# LED.net
KiCad netlist of a schematic drawn in Altium Designer
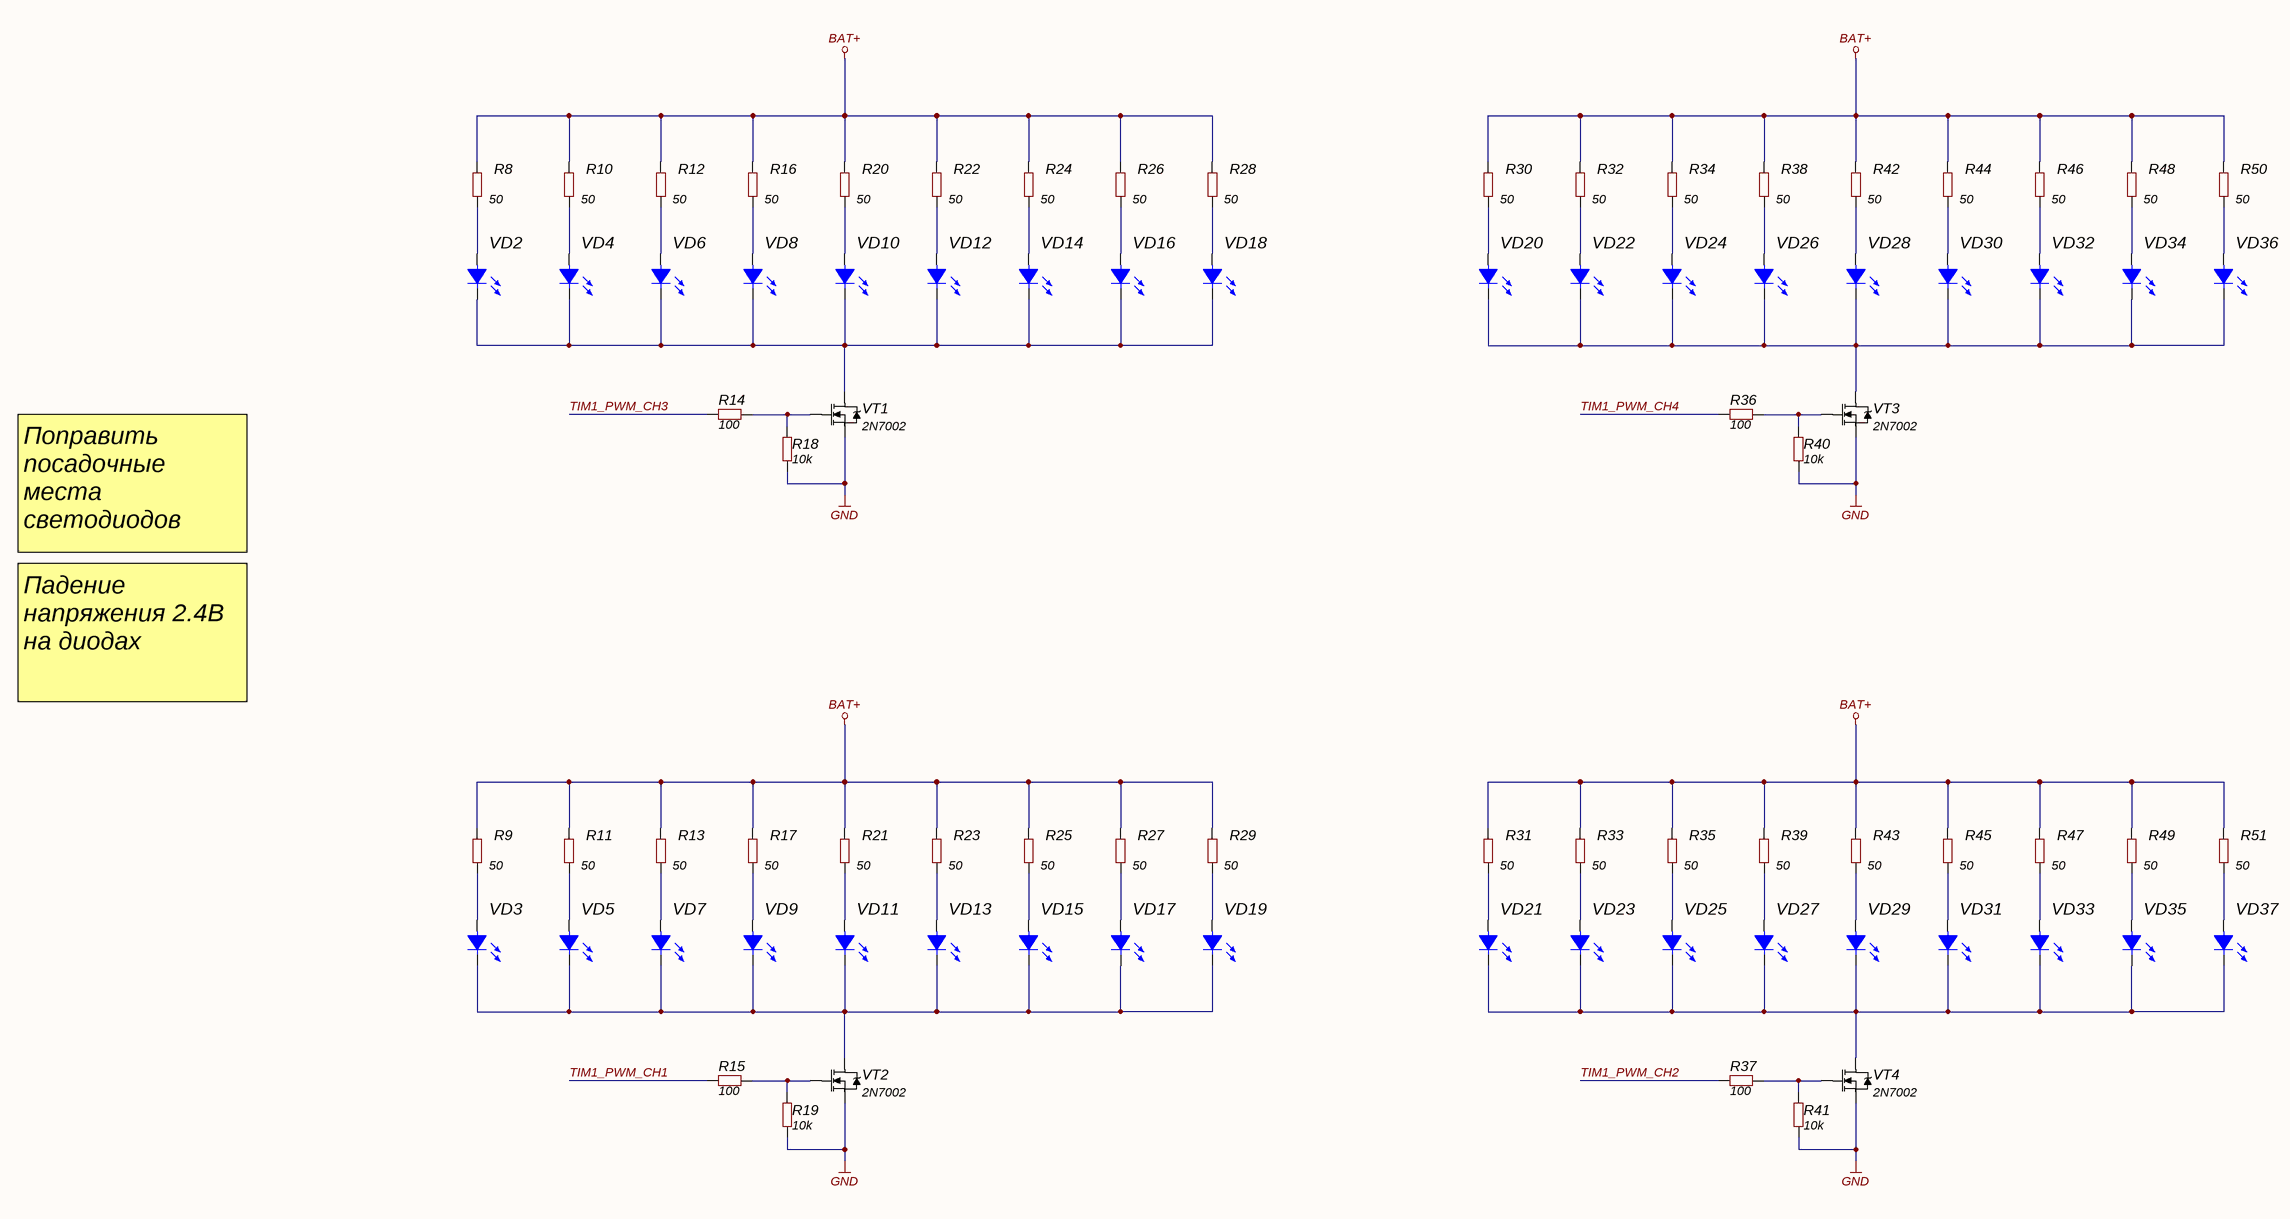
[diagram p0: LED.SchDoc]

(export (version "E")
  (design (tool "Eeschema 10.0.6"))
  (components
    (comp (ref "R8")
      (value "50")
      (footprint "RES: 0603")
      (fields
        (field (name "MANUFACTURER") "Yageo")
        (field (name "PARTNUMBER") "RC0603JR-07100RL")
        (field (name "VALUEMANUFACTURERPARTNUMBER") "Resistor film, 50, , 0603, 0.1W, -55...+125°C")
      )
      (libsource (lib "resistor") (part "Resistor_0603"))
    )
    (comp (ref "R9")
      (value "50")
      (footprint "RES: 0603")
      (fields
        (field (name "MANUFACTURER") "Yageo")
        (field (name "PARTNUMBER") "RC0603JR-07100RL")
        (field (name "VALUEMANUFACTURERPARTNUMBER") "Resistor film, 50, , 0603, 0.1W, -55...+125°C")
      )
      (libsource (lib "resistor") (part "Resistor_0603"))
    )
    (comp (ref "R10")
      (value "50")
      (footprint "RES: 0603")
      (fields
        (field (name "MANUFACTURER") "Yageo")
        (field (name "PARTNUMBER") "RC0603JR-07100RL")
        (field (name "VALUEMANUFACTURERPARTNUMBER") "Resistor film, 50, , 0603, 0.1W, -55...+125°C")
      )
      (libsource (lib "resistor") (part "Resistor_0603"))
    )
    (comp (ref "R11")
      (value "50")
      (footprint "RES: 0603")
      (fields
        (field (name "MANUFACTURER") "Yageo")
        (field (name "PARTNUMBER") "RC0603JR-07100RL")
        (field (name "VALUEMANUFACTURERPARTNUMBER") "Resistor film, 50, , 0603, 0.1W, -55...+125°C")
      )
      (libsource (lib "resistor") (part "Resistor_0603"))
    )
    (comp (ref "R12")
      (value "50")
      (footprint "RES: 0603")
      (fields
        (field (name "MANUFACTURER") "Yageo")
        (field (name "PARTNUMBER") "RC0603JR-07100RL")
        (field (name "VALUEMANUFACTURERPARTNUMBER") "Resistor film, 50, , 0603, 0.1W, -55...+125°C")
      )
      (libsource (lib "resistor") (part "Resistor_0603"))
    )
    (comp (ref "R13")
      (value "50")
      (footprint "RES: 0603")
      (fields
        (field (name "MANUFACTURER") "Yageo")
        (field (name "PARTNUMBER") "RC0603JR-07100RL")
        (field (name "VALUEMANUFACTURERPARTNUMBER") "Resistor film, 50, , 0603, 0.1W, -55...+125°C")
      )
      (libsource (lib "resistor") (part "Resistor_0603"))
    )
    (comp (ref "R14")
      (value "100")
      (footprint "RES: 0603")
      (fields
        (field (name "MANUFACTURER") "Yageo")
        (field (name "PARTNUMBER") "RC0603JR-07100RL")
        (field (name "VALUEMANUFACTURERPARTNUMBER") "Resistor film, 100, , 0603, 0.1W, -55...+125°C")
      )
      (libsource (lib "") (part "Resistor_0603_1"))
    )
    (comp (ref "R15")
      (value "100")
      (footprint "RES: 0603")
      (fields
        (field (name "MANUFACTURER") "Yageo")
        (field (name "PARTNUMBER") "RC0603JR-07100RL")
        (field (name "VALUEMANUFACTURERPARTNUMBER") "Resistor film, 100, , 0603, 0.1W, -55...+125°C")
      )
      (libsource (lib "") (part "Resistor_0603_1"))
    )
    (comp (ref "R16")
      (value "50")
      (footprint "RES: 0603")
      (fields
        (field (name "MANUFACTURER") "Yageo")
        (field (name "PARTNUMBER") "RC0603JR-07100RL")
        (field (name "VALUEMANUFACTURERPARTNUMBER") "Resistor film, 50, , 0603, 0.1W, -55...+125°C")
      )
      (libsource (lib "resistor") (part "Resistor_0603"))
    )
    (comp (ref "R17")
      (value "50")
      (footprint "RES: 0603")
      (fields
        (field (name "MANUFACTURER") "Yageo")
        (field (name "PARTNUMBER") "RC0603JR-07100RL")
        (field (name "VALUEMANUFACTURERPARTNUMBER") "Resistor film, 50, , 0603, 0.1W, -55...+125°C")
      )
      (libsource (lib "resistor") (part "Resistor_0603"))
    )
    (comp (ref "R18")
      (value "10k")
      (footprint "RES: 0603")
      (fields
        (field (name "MANUFACTURER") "Yageo")
        (field (name "PARTNUMBER") "RC0603JR-07100RL")
        (field (name "VALUEMANUFACTURERPARTNUMBER") "Resistor film, 10k, , 0603, 0.1W, -55...+125°C")
      )
      (libsource (lib "resistor") (part "Resistor_0603"))
    )
    (comp (ref "R19")
      (value "10k")
      (footprint "RES: 0603")
      (fields
        (field (name "MANUFACTURER") "Yageo")
        (field (name "PARTNUMBER") "RC0603JR-07100RL")
        (field (name "VALUEMANUFACTURERPARTNUMBER") "Resistor film, 10k, , 0603, 0.1W, -55...+125°C")
      )
      (libsource (lib "resistor") (part "Resistor_0603"))
    )
    (comp (ref "R20")
      (value "50")
      (footprint "RES: 0603")
      (fields
        (field (name "MANUFACTURER") "Yageo")
        (field (name "PARTNUMBER") "RC0603JR-07100RL")
        (field (name "VALUEMANUFACTURERPARTNUMBER") "Resistor film, 50, , 0603, 0.1W, -55...+125°C")
      )
      (libsource (lib "resistor") (part "Resistor_0603"))
    )
    (comp (ref "R21")
      (value "50")
      (footprint "RES: 0603")
      (fields
        (field (name "MANUFACTURER") "Yageo")
        (field (name "PARTNUMBER") "RC0603JR-07100RL")
        (field (name "VALUEMANUFACTURERPARTNUMBER") "Resistor film, 50, , 0603, 0.1W, -55...+125°C")
      )
      (libsource (lib "resistor") (part "Resistor_0603"))
    )
    (comp (ref "R22")
      (value "50")
      (footprint "RES: 0603")
      (fields
        (field (name "MANUFACTURER") "Yageo")
        (field (name "PARTNUMBER") "RC0603JR-07100RL")
        (field (name "VALUEMANUFACTURERPARTNUMBER") "Resistor film, 50, , 0603, 0.1W, -55...+125°C")
      )
      (libsource (lib "resistor") (part "Resistor_0603"))
    )
    (comp (ref "R23")
      (value "50")
      (footprint "RES: 0603")
      (fields
        (field (name "MANUFACTURER") "Yageo")
        (field (name "PARTNUMBER") "RC0603JR-07100RL")
        (field (name "VALUEMANUFACTURERPARTNUMBER") "Resistor film, 50, , 0603, 0.1W, -55...+125°C")
      )
      (libsource (lib "resistor") (part "Resistor_0603"))
    )
    (comp (ref "R24")
      (value "50")
      (footprint "RES: 0603")
      (fields
        (field (name "MANUFACTURER") "Yageo")
        (field (name "PARTNUMBER") "RC0603JR-07100RL")
        (field (name "VALUEMANUFACTURERPARTNUMBER") "Resistor film, 50, , 0603, 0.1W, -55...+125°C")
      )
      (libsource (lib "resistor") (part "Resistor_0603"))
    )
    (comp (ref "R25")
      (value "50")
      (footprint "RES: 0603")
      (fields
        (field (name "MANUFACTURER") "Yageo")
        (field (name "PARTNUMBER") "RC0603JR-07100RL")
        (field (name "VALUEMANUFACTURERPARTNUMBER") "Resistor film, 50, , 0603, 0.1W, -55...+125°C")
      )
      (libsource (lib "resistor") (part "Resistor_0603"))
    )
    (comp (ref "R26")
      (value "50")
      (footprint "RES: 0603")
      (fields
        (field (name "MANUFACTURER") "Yageo")
        (field (name "PARTNUMBER") "RC0603JR-07100RL")
        (field (name "VALUEMANUFACTURERPARTNUMBER") "Resistor film, 50, , 0603, 0.1W, -55...+125°C")
      )
      (libsource (lib "resistor") (part "Resistor_0603"))
    )
    (comp (ref "R27")
      (value "50")
      (footprint "RES: 0603")
      (fields
        (field (name "MANUFACTURER") "Yageo")
        (field (name "PARTNUMBER") "RC0603JR-07100RL")
        (field (name "VALUEMANUFACTURERPARTNUMBER") "Resistor film, 50, , 0603, 0.1W, -55...+125°C")
      )
      (libsource (lib "resistor") (part "Resistor_0603"))
    )
    (comp (ref "R28")
      (value "50")
      (footprint "RES: 0603")
      (fields
        (field (name "MANUFACTURER") "Yageo")
        (field (name "PARTNUMBER") "RC0603JR-07100RL")
        (field (name "VALUEMANUFACTURERPARTNUMBER") "Resistor film, 50, , 0603, 0.1W, -55...+125°C")
      )
      (libsource (lib "resistor") (part "Resistor_0603"))
    )
    (comp (ref "R29")
      (value "50")
      (footprint "RES: 0603")
      (fields
        (field (name "MANUFACTURER") "Yageo")
        (field (name "PARTNUMBER") "RC0603JR-07100RL")
        (field (name "VALUEMANUFACTURERPARTNUMBER") "Resistor film, 50, , 0603, 0.1W, -55...+125°C")
      )
      (libsource (lib "resistor") (part "Resistor_0603"))
    )
    (comp (ref "R30")
      (value "50")
      (footprint "RES: 0603")
      (fields
        (field (name "MANUFACTURER") "Yageo")
        (field (name "PARTNUMBER") "RC0603JR-07100RL")
        (field (name "VALUEMANUFACTURERPARTNUMBER") "Resistor film, 50, , 0603, 0.1W, -55...+125°C")
      )
      (libsource (lib "resistor") (part "Resistor_0603"))
    )
    (comp (ref "R31")
      (value "50")
      (footprint "RES: 0603")
      (fields
        (field (name "MANUFACTURER") "Yageo")
        (field (name "PARTNUMBER") "RC0603JR-07100RL")
        (field (name "VALUEMANUFACTURERPARTNUMBER") "Resistor film, 50, , 0603, 0.1W, -55...+125°C")
      )
      (libsource (lib "resistor") (part "Resistor_0603"))
    )
    (comp (ref "R32")
      (value "50")
      (footprint "RES: 0603")
      (fields
        (field (name "MANUFACTURER") "Yageo")
        (field (name "PARTNUMBER") "RC0603JR-07100RL")
        (field (name "VALUEMANUFACTURERPARTNUMBER") "Resistor film, 50, , 0603, 0.1W, -55...+125°C")
      )
      (libsource (lib "resistor") (part "Resistor_0603"))
    )
    (comp (ref "R33")
      (value "50")
      (footprint "RES: 0603")
      (fields
        (field (name "MANUFACTURER") "Yageo")
        (field (name "PARTNUMBER") "RC0603JR-07100RL")
        (field (name "VALUEMANUFACTURERPARTNUMBER") "Resistor film, 50, , 0603, 0.1W, -55...+125°C")
      )
      (libsource (lib "resistor") (part "Resistor_0603"))
    )
    (comp (ref "R34")
      (value "50")
      (footprint "RES: 0603")
      (fields
        (field (name "MANUFACTURER") "Yageo")
        (field (name "PARTNUMBER") "RC0603JR-07100RL")
        (field (name "VALUEMANUFACTURERPARTNUMBER") "Resistor film, 50, , 0603, 0.1W, -55...+125°C")
      )
      (libsource (lib "resistor") (part "Resistor_0603"))
    )
    (comp (ref "R35")
      (value "50")
      (footprint "RES: 0603")
      (fields
        (field (name "MANUFACTURER") "Yageo")
        (field (name "PARTNUMBER") "RC0603JR-07100RL")
        (field (name "VALUEMANUFACTURERPARTNUMBER") "Resistor film, 50, , 0603, 0.1W, -55...+125°C")
      )
      (libsource (lib "resistor") (part "Resistor_0603"))
    )
    (comp (ref "R36")
      (value "100")
      (footprint "RES: 0603")
      (fields
        (field (name "MANUFACTURER") "Yageo")
        (field (name "PARTNUMBER") "RC0603JR-07100RL")
        (field (name "VALUEMANUFACTURERPARTNUMBER") "Resistor film, 100, , 0603, 0.1W, -55...+125°C")
      )
      (libsource (lib "") (part "Resistor_0603_1"))
    )
    (comp (ref "R37")
      (value "100")
      (footprint "RES: 0603")
      (fields
        (field (name "MANUFACTURER") "Yageo")
        (field (name "PARTNUMBER") "RC0603JR-07100RL")
        (field (name "VALUEMANUFACTURERPARTNUMBER") "Resistor film, 100, , 0603, 0.1W, -55...+125°C")
      )
      (libsource (lib "") (part "Resistor_0603_1"))
    )
    (comp (ref "R38")
      (value "50")
      (footprint "RES: 0603")
      (fields
        (field (name "MANUFACTURER") "Yageo")
        (field (name "PARTNUMBER") "RC0603JR-07100RL")
        (field (name "VALUEMANUFACTURERPARTNUMBER") "Resistor film, 50, , 0603, 0.1W, -55...+125°C")
      )
      (libsource (lib "resistor") (part "Resistor_0603"))
    )
    (comp (ref "R39")
      (value "50")
      (footprint "RES: 0603")
      (fields
        (field (name "MANUFACTURER") "Yageo")
        (field (name "PARTNUMBER") "RC0603JR-07100RL")
        (field (name "VALUEMANUFACTURERPARTNUMBER") "Resistor film, 50, , 0603, 0.1W, -55...+125°C")
      )
      (libsource (lib "resistor") (part "Resistor_0603"))
    )
    (comp (ref "R40")
      (value "10k")
      (footprint "RES: 0603")
      (fields
        (field (name "MANUFACTURER") "Yageo")
        (field (name "PARTNUMBER") "RC0603JR-07100RL")
        (field (name "VALUEMANUFACTURERPARTNUMBER") "Resistor film, 10k, , 0603, 0.1W, -55...+125°C")
      )
      (libsource (lib "resistor") (part "Resistor_0603"))
    )
    (comp (ref "R41")
      (value "10k")
      (footprint "RES: 0603")
      (fields
        (field (name "MANUFACTURER") "Yageo")
        (field (name "PARTNUMBER") "RC0603JR-07100RL")
        (field (name "VALUEMANUFACTURERPARTNUMBER") "Resistor film, 10k, , 0603, 0.1W, -55...+125°C")
      )
      (libsource (lib "resistor") (part "Resistor_0603"))
    )
    (comp (ref "R42")
      (value "50")
      (footprint "RES: 0603")
      (fields
        (field (name "MANUFACTURER") "Yageo")
        (field (name "PARTNUMBER") "RC0603JR-07100RL")
        (field (name "VALUEMANUFACTURERPARTNUMBER") "Resistor film, 50, , 0603, 0.1W, -55...+125°C")
      )
      (libsource (lib "resistor") (part "Resistor_0603"))
    )
    (comp (ref "R43")
      (value "50")
      (footprint "RES: 0603")
      (fields
        (field (name "MANUFACTURER") "Yageo")
        (field (name "PARTNUMBER") "RC0603JR-07100RL")
        (field (name "VALUEMANUFACTURERPARTNUMBER") "Resistor film, 50, , 0603, 0.1W, -55...+125°C")
      )
      (libsource (lib "resistor") (part "Resistor_0603"))
    )
    (comp (ref "R44")
      (value "50")
      (footprint "RES: 0603")
      (fields
        (field (name "MANUFACTURER") "Yageo")
        (field (name "PARTNUMBER") "RC0603JR-07100RL")
        (field (name "VALUEMANUFACTURERPARTNUMBER") "Resistor film, 50, , 0603, 0.1W, -55...+125°C")
      )
      (libsource (lib "resistor") (part "Resistor_0603"))
    )
    (comp (ref "R45")
      (value "50")
      (footprint "RES: 0603")
      (fields
        (field (name "MANUFACTURER") "Yageo")
        (field (name "PARTNUMBER") "RC0603JR-07100RL")
        (field (name "VALUEMANUFACTURERPARTNUMBER") "Resistor film, 50, , 0603, 0.1W, -55...+125°C")
      )
      (libsource (lib "resistor") (part "Resistor_0603"))
    )
    (comp (ref "R46")
      (value "50")
      (footprint "RES: 0603")
      (fields
        (field (name "MANUFACTURER") "Yageo")
        (field (name "PARTNUMBER") "RC0603JR-07100RL")
        (field (name "VALUEMANUFACTURERPARTNUMBER") "Resistor film, 50, , 0603, 0.1W, -55...+125°C")
      )
      (libsource (lib "resistor") (part "Resistor_0603"))
    )
    (comp (ref "R47")
      (value "50")
      (footprint "RES: 0603")
      (fields
        (field (name "MANUFACTURER") "Yageo")
        (field (name "PARTNUMBER") "RC0603JR-07100RL")
        (field (name "VALUEMANUFACTURERPARTNUMBER") "Resistor film, 50, , 0603, 0.1W, -55...+125°C")
      )
      (libsource (lib "resistor") (part "Resistor_0603"))
    )
    (comp (ref "R48")
      (value "50")
      (footprint "RES: 0603")
      (fields
        (field (name "MANUFACTURER") "Yageo")
        (field (name "PARTNUMBER") "RC0603JR-07100RL")
        (field (name "VALUEMANUFACTURERPARTNUMBER") "Resistor film, 50, , 0603, 0.1W, -55...+125°C")
      )
      (libsource (lib "resistor") (part "Resistor_0603"))
    )
    (comp (ref "R49")
      (value "50")
      (footprint "RES: 0603")
      (fields
        (field (name "MANUFACTURER") "Yageo")
        (field (name "PARTNUMBER") "RC0603JR-07100RL")
        (field (name "VALUEMANUFACTURERPARTNUMBER") "Resistor film, 50, , 0603, 0.1W, -55...+125°C")
      )
      (libsource (lib "resistor") (part "Resistor_0603"))
    )
    (comp (ref "R50")
      (value "50")
      (footprint "RES: 0603")
      (fields
        (field (name "MANUFACTURER") "Yageo")
        (field (name "PARTNUMBER") "RC0603JR-07100RL")
        (field (name "VALUEMANUFACTURERPARTNUMBER") "Resistor film, 50, , 0603, 0.1W, -55...+125°C")
      )
      (libsource (lib "resistor") (part "Resistor_0603"))
    )
    (comp (ref "R51")
      (value "50")
      (footprint "RES: 0603")
      (fields
        (field (name "MANUFACTURER") "Yageo")
        (field (name "PARTNUMBER") "RC0603JR-07100RL")
        (field (name "VALUEMANUFACTURERPARTNUMBER") "Resistor film, 50, , 0603, 0.1W, -55...+125°C")
      )
      (libsource (lib "resistor") (part "Resistor_0603"))
    )
    (comp (ref "VD2")
      (value "~")
      (footprint "LED: 1206Y")
      (fields (field (name "VALUEMANUFACTURERPARTNUMBER") "LED, Green, *, *, *, -55...+150°C"))
      (libsource (lib "diode") (part "LED_single"))
    )
    (comp (ref "VD3")
      (value "~")
      (footprint "LED: 1206Y")
      (fields (field (name "VALUEMANUFACTURERPARTNUMBER") "LED, Green, *, *, *, -55...+150°C"))
      (libsource (lib "diode") (part "LED_single"))
    )
    (comp (ref "VD4")
      (value "~")
      (footprint "LED: 1206Y")
      (fields (field (name "VALUEMANUFACTURERPARTNUMBER") "LED, Green, *, *, *, -55...+150°C"))
      (libsource (lib "diode") (part "LED_single"))
    )
    (comp (ref "VD5")
      (value "~")
      (footprint "LED: 1206Y")
      (fields (field (name "VALUEMANUFACTURERPARTNUMBER") "LED, Green, *, *, *, -55...+150°C"))
      (libsource (lib "diode") (part "LED_single"))
    )
    (comp (ref "VD6")
      (value "~")
      (footprint "LED: 1206Y")
      (fields (field (name "VALUEMANUFACTURERPARTNUMBER") "LED, Green, *, *, *, -55...+150°C"))
      (libsource (lib "diode") (part "LED_single"))
    )
    (comp (ref "VD7")
      (value "~")
      (footprint "LED: 1206Y")
      (fields (field (name "VALUEMANUFACTURERPARTNUMBER") "LED, Green, *, *, *, -55...+150°C"))
      (libsource (lib "diode") (part "LED_single"))
    )
    (comp (ref "VD8")
      (value "~")
      (footprint "LED: 1206Y")
      (fields (field (name "VALUEMANUFACTURERPARTNUMBER") "LED, Green, *, *, *, -55...+150°C"))
      (libsource (lib "diode") (part "LED_single"))
    )
    (comp (ref "VD9")
      (value "~")
      (footprint "LED: 1206Y")
      (fields (field (name "VALUEMANUFACTURERPARTNUMBER") "LED, Green, *, *, *, -55...+150°C"))
      (libsource (lib "diode") (part "LED_single"))
    )
    (comp (ref "VD10")
      (value "~")
      (footprint "LED: 1206Y")
      (fields (field (name "VALUEMANUFACTURERPARTNUMBER") "LED, Green, *, *, *, -55...+150°C"))
      (libsource (lib "diode") (part "LED_single"))
    )
    (comp (ref "VD11")
      (value "~")
      (footprint "LED: 1206Y")
      (fields (field (name "VALUEMANUFACTURERPARTNUMBER") "LED, Green, *, *, *, -55...+150°C"))
      (libsource (lib "diode") (part "LED_single"))
    )
    (comp (ref "VD12")
      (value "~")
      (footprint "LED: 1206Y")
      (fields (field (name "VALUEMANUFACTURERPARTNUMBER") "LED, Green, *, *, *, -55...+150°C"))
      (libsource (lib "diode") (part "LED_single"))
    )
    (comp (ref "VD13")
      (value "~")
      (footprint "LED: 1206Y")
      (fields (field (name "VALUEMANUFACTURERPARTNUMBER") "LED, Green, *, *, *, -55...+150°C"))
      (libsource (lib "diode") (part "LED_single"))
    )
    (comp (ref "VD14")
      (value "~")
      (footprint "LED: 1206Y")
      (fields (field (name "VALUEMANUFACTURERPARTNUMBER") "LED, Green, *, *, *, -55...+150°C"))
      (libsource (lib "diode") (part "LED_single"))
    )
    (comp (ref "VD15")
      (value "~")
      (footprint "LED: 1206Y")
      (fields (field (name "VALUEMANUFACTURERPARTNUMBER") "LED, Green, *, *, *, -55...+150°C"))
      (libsource (lib "diode") (part "LED_single"))
    )
    (comp (ref "VD16")
      (value "~")
      (footprint "LED: 1206Y")
      (fields (field (name "VALUEMANUFACTURERPARTNUMBER") "LED, Green, *, *, *, -55...+150°C"))
      (libsource (lib "diode") (part "LED_single"))
    )
    (comp (ref "VD17")
      (value "~")
      (footprint "LED: 1206Y")
      (fields (field (name "VALUEMANUFACTURERPARTNUMBER") "LED, Green, *, *, *, -55...+150°C"))
      (libsource (lib "diode") (part "LED_single"))
    )
    (comp (ref "VD18")
      (value "~")
      (footprint "LED: 1206Y")
      (fields (field (name "VALUEMANUFACTURERPARTNUMBER") "LED, Green, *, *, *, -55...+150°C"))
      (libsource (lib "diode") (part "LED_single"))
    )
    (comp (ref "VD19")
      (value "~")
      (footprint "LED: 1206Y")
      (fields (field (name "VALUEMANUFACTURERPARTNUMBER") "LED, Green, *, *, *, -55...+150°C"))
      (libsource (lib "diode") (part "LED_single"))
    )
    (comp (ref "VD20")
      (value "~")
      (footprint "LED: 1206Y")
      (fields (field (name "VALUEMANUFACTURERPARTNUMBER") "LED, Green, *, *, *, -55...+150°C"))
      (libsource (lib "diode") (part "LED_single"))
    )
    (comp (ref "VD21")
      (value "~")
      (footprint "LED: 1206Y")
      (fields (field (name "VALUEMANUFACTURERPARTNUMBER") "LED, Green, *, *, *, -55...+150°C"))
      (libsource (lib "diode") (part "LED_single"))
    )
    (comp (ref "VD22")
      (value "~")
      (footprint "LED: 1206Y")
      (fields (field (name "VALUEMANUFACTURERPARTNUMBER") "LED, Green, *, *, *, -55...+150°C"))
      (libsource (lib "diode") (part "LED_single"))
    )
    (comp (ref "VD23")
      (value "~")
      (footprint "LED: 1206Y")
      (fields (field (name "VALUEMANUFACTURERPARTNUMBER") "LED, Green, *, *, *, -55...+150°C"))
      (libsource (lib "diode") (part "LED_single"))
    )
    (comp (ref "VD24")
      (value "~")
      (footprint "LED: 1206Y")
      (fields (field (name "VALUEMANUFACTURERPARTNUMBER") "LED, Green, *, *, *, -55...+150°C"))
      (libsource (lib "diode") (part "LED_single"))
    )
    (comp (ref "VD25")
      (value "~")
      (footprint "LED: 1206Y")
      (fields (field (name "VALUEMANUFACTURERPARTNUMBER") "LED, Green, *, *, *, -55...+150°C"))
      (libsource (lib "diode") (part "LED_single"))
    )
    (comp (ref "VD26")
      (value "~")
      (footprint "LED: 1206Y")
      (fields (field (name "VALUEMANUFACTURERPARTNUMBER") "LED, Green, *, *, *, -55...+150°C"))
      (libsource (lib "diode") (part "LED_single"))
    )
    (comp (ref "VD27")
      (value "~")
      (footprint "LED: 1206Y")
      (fields (field (name "VALUEMANUFACTURERPARTNUMBER") "LED, Green, *, *, *, -55...+150°C"))
      (libsource (lib "diode") (part "LED_single"))
    )
    (comp (ref "VD28")
      (value "~")
      (footprint "LED: 1206Y")
      (fields (field (name "VALUEMANUFACTURERPARTNUMBER") "LED, Green, *, *, *, -55...+150°C"))
      (libsource (lib "diode") (part "LED_single"))
    )
    (comp (ref "VD29")
      (value "~")
      (footprint "LED: 1206Y")
      (fields (field (name "VALUEMANUFACTURERPARTNUMBER") "LED, Green, *, *, *, -55...+150°C"))
      (libsource (lib "diode") (part "LED_single"))
    )
    (comp (ref "VD30")
      (value "~")
      (footprint "LED: 1206Y")
      (fields (field (name "VALUEMANUFACTURERPARTNUMBER") "LED, Green, *, *, *, -55...+150°C"))
      (libsource (lib "diode") (part "LED_single"))
    )
    (comp (ref "VD31")
      (value "~")
      (footprint "LED: 1206Y")
      (fields (field (name "VALUEMANUFACTURERPARTNUMBER") "LED, Green, *, *, *, -55...+150°C"))
      (libsource (lib "diode") (part "LED_single"))
    )
    (comp (ref "VD32")
      (value "~")
      (footprint "LED: 1206Y")
      (fields (field (name "VALUEMANUFACTURERPARTNUMBER") "LED, Green, *, *, *, -55...+150°C"))
      (libsource (lib "diode") (part "LED_single"))
    )
    (comp (ref "VD33")
      (value "~")
      (footprint "LED: 1206Y")
      (fields (field (name "VALUEMANUFACTURERPARTNUMBER") "LED, Green, *, *, *, -55...+150°C"))
      (libsource (lib "diode") (part "LED_single"))
    )
    (comp (ref "VD34")
      (value "~")
      (footprint "LED: 1206Y")
      (fields (field (name "VALUEMANUFACTURERPARTNUMBER") "LED, Green, *, *, *, -55...+150°C"))
      (libsource (lib "diode") (part "LED_single"))
    )
    (comp (ref "VD35")
      (value "~")
      (footprint "LED: 1206Y")
      (fields (field (name "VALUEMANUFACTURERPARTNUMBER") "LED, Green, *, *, *, -55...+150°C"))
      (libsource (lib "diode") (part "LED_single"))
    )
    (comp (ref "VD36")
      (value "~")
      (footprint "LED: 1206Y")
      (fields (field (name "VALUEMANUFACTURERPARTNUMBER") "LED, Green, *, *, *, -55...+150°C"))
      (libsource (lib "diode") (part "LED_single"))
    )
    (comp (ref "VD37")
      (value "~")
      (footprint "LED: 1206Y")
      (fields (field (name "VALUEMANUFACTURERPARTNUMBER") "LED, Green, *, *, *, -55...+150°C"))
      (libsource (lib "diode") (part "LED_single"))
    )
    (comp (ref "VT1")
      (value "~")
      (footprint "SOT23")
      (fields
        (field (name "MANUFACTURER") "Infineon Technologies")
        (field (name "VALUEMANUFACTURERPARTNUMBER") "MOSFET N-channel transistor, 80V, 7A, 9.1nC, 2.5W, 34mOhm, 756pF, 8-TDSON, -55...+150°C")
        (field (name "PARTNUMBER") "2N7002")
      )
      (libsource (lib "transistor") (part "MOSFET_N_132"))
    )
    (comp (ref "VT2")
      (value "~")
      (footprint "SOT23")
      (fields
        (field (name "MANUFACTURER") "Infineon Technologies")
        (field (name "VALUEMANUFACTURERPARTNUMBER") "MOSFET N-channel transistor, 80V, 7A, 9.1nC, 2.5W, 34mOhm, 756pF, 8-TDSON, -55...+150°C")
        (field (name "PARTNUMBER") "2N7002")
      )
      (libsource (lib "transistor") (part "MOSFET_N_132"))
    )
    (comp (ref "VT3")
      (value "~")
      (footprint "SOT23")
      (fields
        (field (name "MANUFACTURER") "Infineon Technologies")
        (field (name "VALUEMANUFACTURERPARTNUMBER") "MOSFET N-channel transistor, 80V, 7A, 9.1nC, 2.5W, 34mOhm, 756pF, 8-TDSON, -55...+150°C")
        (field (name "PARTNUMBER") "2N7002")
      )
      (libsource (lib "transistor") (part "MOSFET_N_132"))
    )
    (comp (ref "VT4")
      (value "~")
      (footprint "SOT23")
      (fields
        (field (name "MANUFACTURER") "Infineon Technologies")
        (field (name "VALUEMANUFACTURERPARTNUMBER") "MOSFET N-channel transistor, 80V, 7A, 9.1nC, 2.5W, 34mOhm, 756pF, 8-TDSON, -55...+150°C")
        (field (name "PARTNUMBER") "2N7002")
      )
      (libsource (lib "transistor") (part "MOSFET_N_132"))
    )
  )
  (nets
    (net (code "1") (name "/TIM1_PWM_CH1") (class "Default")
      (node (ref "R15") (pin "1") (pinfunction "1_1") (pintype "passive"))
    )
    (net (code "2") (name "/TIM1_PWM_CH2") (class "Default")
      (node (ref "R37") (pin "1") (pinfunction "1_1") (pintype "passive"))
    )
    (net (code "3") (name "/TIM1_PWM_CH3") (class "Default")
      (node (ref "R14") (pin "1") (pinfunction "1_1") (pintype "passive"))
    )
    (net (code "4") (name "/TIM1_PWM_CH4") (class "Default")
      (node (ref "R36") (pin "1") (pinfunction "1_1") (pintype "passive"))
    )
    (net (code "5") (name "BAT+") (class "Default")
      (node (ref "R10") (pin "2") (pinfunction "2_2") (pintype "passive"))
      (node (ref "R11") (pin "2") (pinfunction "2_2") (pintype "passive"))
      (node (ref "R12") (pin "2") (pinfunction "2_2") (pintype "passive"))
      (node (ref "R13") (pin "2") (pinfunction "2_2") (pintype "passive"))
      (node (ref "R16") (pin "2") (pinfunction "2_2") (pintype "passive"))
      (node (ref "R17") (pin "2") (pinfunction "2_2") (pintype "passive"))
      (node (ref "R20") (pin "2") (pinfunction "2_2") (pintype "passive"))
      (node (ref "R21") (pin "2") (pinfunction "2_2") (pintype "passive"))
      (node (ref "R22") (pin "2") (pinfunction "2_2") (pintype "passive"))
      (node (ref "R23") (pin "2") (pinfunction "2_2") (pintype "passive"))
      (node (ref "R24") (pin "2") (pinfunction "2_2") (pintype "passive"))
      (node (ref "R25") (pin "2") (pinfunction "2_2") (pintype "passive"))
      (node (ref "R26") (pin "2") (pinfunction "2_2") (pintype "passive"))
      (node (ref "R27") (pin "2") (pinfunction "2_2") (pintype "passive"))
      (node (ref "R28") (pin "2") (pinfunction "2_2") (pintype "passive"))
      (node (ref "R29") (pin "2") (pinfunction "2_2") (pintype "passive"))
      (node (ref "R30") (pin "2") (pinfunction "2_2") (pintype "passive"))
      (node (ref "R31") (pin "2") (pinfunction "2_2") (pintype "passive"))
      (node (ref "R32") (pin "2") (pinfunction "2_2") (pintype "passive"))
      (node (ref "R33") (pin "2") (pinfunction "2_2") (pintype "passive"))
      (node (ref "R34") (pin "2") (pinfunction "2_2") (pintype "passive"))
      (node (ref "R35") (pin "2") (pinfunction "2_2") (pintype "passive"))
      (node (ref "R38") (pin "2") (pinfunction "2_2") (pintype "passive"))
      (node (ref "R39") (pin "2") (pinfunction "2_2") (pintype "passive"))
      (node (ref "R42") (pin "2") (pinfunction "2_2") (pintype "passive"))
      (node (ref "R43") (pin "2") (pinfunction "2_2") (pintype "passive"))
      (node (ref "R44") (pin "2") (pinfunction "2_2") (pintype "passive"))
      (node (ref "R45") (pin "2") (pinfunction "2_2") (pintype "passive"))
      (node (ref "R46") (pin "2") (pinfunction "2_2") (pintype "passive"))
      (node (ref "R47") (pin "2") (pinfunction "2_2") (pintype "passive"))
      (node (ref "R48") (pin "2") (pinfunction "2_2") (pintype "passive"))
      (node (ref "R49") (pin "2") (pinfunction "2_2") (pintype "passive"))
      (node (ref "R50") (pin "2") (pinfunction "2_2") (pintype "passive"))
      (node (ref "R51") (pin "2") (pinfunction "2_2") (pintype "passive"))
      (node (ref "R8") (pin "2") (pinfunction "2_2") (pintype "passive"))
      (node (ref "R9") (pin "2") (pinfunction "2_2") (pintype "passive"))
    )
    (net (code "6") (name "GND") (class "Default")
      (node (ref "R18") (pin "1") (pinfunction "1_1") (pintype "passive"))
      (node (ref "R19") (pin "1") (pinfunction "1_1") (pintype "passive"))
      (node (ref "R40") (pin "1") (pinfunction "1_1") (pintype "passive"))
      (node (ref "R41") (pin "1") (pinfunction "1_1") (pintype "passive"))
      (node (ref "VT1") (pin "2") (pinfunction "S_2") (pintype "passive"))
      (node (ref "VT2") (pin "2") (pinfunction "S_2") (pintype "passive"))
      (node (ref "VT3") (pin "2") (pinfunction "S_2") (pintype "passive"))
      (node (ref "VT4") (pin "2") (pinfunction "S_2") (pintype "passive"))
    )
    (net (code "7") (name "Net-(VD2-A)") (class "Default")
      (node (ref "R8") (pin "1") (pinfunction "1_1") (pintype "passive"))
      (node (ref "VD2") (pin "1") (pinfunction "A_1") (pintype "passive"))
    )
    (net (code "8") (name "Net-(VD3-A)") (class "Default")
      (node (ref "R9") (pin "1") (pinfunction "1_1") (pintype "passive"))
      (node (ref "VD3") (pin "1") (pinfunction "A_1") (pintype "passive"))
    )
    (net (code "9") (name "Net-(VD4-A)") (class "Default")
      (node (ref "R10") (pin "1") (pinfunction "1_1") (pintype "passive"))
      (node (ref "VD4") (pin "1") (pinfunction "A_1") (pintype "passive"))
    )
    (net (code "10") (name "Net-(VD5-A)") (class "Default")
      (node (ref "R11") (pin "1") (pinfunction "1_1") (pintype "passive"))
      (node (ref "VD5") (pin "1") (pinfunction "A_1") (pintype "passive"))
    )
    (net (code "11") (name "Net-(VD6-A)") (class "Default")
      (node (ref "R12") (pin "1") (pinfunction "1_1") (pintype "passive"))
      (node (ref "VD6") (pin "1") (pinfunction "A_1") (pintype "passive"))
    )
    (net (code "12") (name "Net-(VD7-A)") (class "Default")
      (node (ref "R13") (pin "1") (pinfunction "1_1") (pintype "passive"))
      (node (ref "VD7") (pin "1") (pinfunction "A_1") (pintype "passive"))
    )
    (net (code "13") (name "Net-(VD8-A)") (class "Default")
      (node (ref "R16") (pin "1") (pinfunction "1_1") (pintype "passive"))
      (node (ref "VD8") (pin "1") (pinfunction "A_1") (pintype "passive"))
    )
    (net (code "14") (name "Net-(VD9-A)") (class "Default")
      (node (ref "R17") (pin "1") (pinfunction "1_1") (pintype "passive"))
      (node (ref "VD9") (pin "1") (pinfunction "A_1") (pintype "passive"))
    )
    (net (code "15") (name "Net-(VD10-A)") (class "Default")
      (node (ref "R20") (pin "1") (pinfunction "1_1") (pintype "passive"))
      (node (ref "VD10") (pin "1") (pinfunction "A_1") (pintype "passive"))
    )
    (net (code "16") (name "Net-(VD10-C)") (class "Default")
      (node (ref "VD10") (pin "2") (pinfunction "C_2") (pintype "passive"))
      (node (ref "VD12") (pin "2") (pinfunction "C_2") (pintype "passive"))
      (node (ref "VD14") (pin "2") (pinfunction "C_2") (pintype "passive"))
      (node (ref "VD16") (pin "2") (pinfunction "C_2") (pintype "passive"))
      (node (ref "VD18") (pin "2") (pinfunction "C_2") (pintype "passive"))
      (node (ref "VD2") (pin "2") (pinfunction "C_2") (pintype "passive"))
      (node (ref "VD4") (pin "2") (pinfunction "C_2") (pintype "passive"))
      (node (ref "VD6") (pin "2") (pinfunction "C_2") (pintype "passive"))
      (node (ref "VD8") (pin "2") (pinfunction "C_2") (pintype "passive"))
      (node (ref "VT1") (pin "3") (pinfunction "D_3") (pintype "passive"))
    )
    (net (code "17") (name "Net-(VD11-A)") (class "Default")
      (node (ref "R21") (pin "1") (pinfunction "1_1") (pintype "passive"))
      (node (ref "VD11") (pin "1") (pinfunction "A_1") (pintype "passive"))
    )
    (net (code "18") (name "Net-(VD11-C)") (class "Default")
      (node (ref "VD11") (pin "2") (pinfunction "C_2") (pintype "passive"))
      (node (ref "VD13") (pin "2") (pinfunction "C_2") (pintype "passive"))
      (node (ref "VD15") (pin "2") (pinfunction "C_2") (pintype "passive"))
      (node (ref "VD17") (pin "2") (pinfunction "C_2") (pintype "passive"))
      (node (ref "VD19") (pin "2") (pinfunction "C_2") (pintype "passive"))
      (node (ref "VD3") (pin "2") (pinfunction "C_2") (pintype "passive"))
      (node (ref "VD5") (pin "2") (pinfunction "C_2") (pintype "passive"))
      (node (ref "VD7") (pin "2") (pinfunction "C_2") (pintype "passive"))
      (node (ref "VD9") (pin "2") (pinfunction "C_2") (pintype "passive"))
      (node (ref "VT2") (pin "3") (pinfunction "D_3") (pintype "passive"))
    )
    (net (code "19") (name "Net-(VD12-A)") (class "Default")
      (node (ref "R22") (pin "1") (pinfunction "1_1") (pintype "passive"))
      (node (ref "VD12") (pin "1") (pinfunction "A_1") (pintype "passive"))
    )
    (net (code "20") (name "Net-(VD13-A)") (class "Default")
      (node (ref "R23") (pin "1") (pinfunction "1_1") (pintype "passive"))
      (node (ref "VD13") (pin "1") (pinfunction "A_1") (pintype "passive"))
    )
    (net (code "21") (name "Net-(VD14-A)") (class "Default")
      (node (ref "R24") (pin "1") (pinfunction "1_1") (pintype "passive"))
      (node (ref "VD14") (pin "1") (pinfunction "A_1") (pintype "passive"))
    )
    (net (code "22") (name "Net-(VD15-A)") (class "Default")
      (node (ref "R25") (pin "1") (pinfunction "1_1") (pintype "passive"))
      (node (ref "VD15") (pin "1") (pinfunction "A_1") (pintype "passive"))
    )
    (net (code "23") (name "Net-(VD16-A)") (class "Default")
      (node (ref "R26") (pin "1") (pinfunction "1_1") (pintype "passive"))
      (node (ref "VD16") (pin "1") (pinfunction "A_1") (pintype "passive"))
    )
    (net (code "24") (name "Net-(VD17-A)") (class "Default")
      (node (ref "R27") (pin "1") (pinfunction "1_1") (pintype "passive"))
      (node (ref "VD17") (pin "1") (pinfunction "A_1") (pintype "passive"))
    )
    (net (code "25") (name "Net-(VD18-A)") (class "Default")
      (node (ref "R28") (pin "1") (pinfunction "1_1") (pintype "passive"))
      (node (ref "VD18") (pin "1") (pinfunction "A_1") (pintype "passive"))
    )
    (net (code "26") (name "Net-(VD19-A)") (class "Default")
      (node (ref "R29") (pin "1") (pinfunction "1_1") (pintype "passive"))
      (node (ref "VD19") (pin "1") (pinfunction "A_1") (pintype "passive"))
    )
    (net (code "27") (name "Net-(VD20-A)") (class "Default")
      (node (ref "R30") (pin "1") (pinfunction "1_1") (pintype "passive"))
      (node (ref "VD20") (pin "1") (pinfunction "A_1") (pintype "passive"))
    )
    (net (code "28") (name "Net-(VD20-C)") (class "Default")
      (node (ref "VD20") (pin "2") (pinfunction "C_2") (pintype "passive"))
      (node (ref "VD22") (pin "2") (pinfunction "C_2") (pintype "passive"))
      (node (ref "VD24") (pin "2") (pinfunction "C_2") (pintype "passive"))
      (node (ref "VD26") (pin "2") (pinfunction "C_2") (pintype "passive"))
      (node (ref "VD28") (pin "2") (pinfunction "C_2") (pintype "passive"))
      (node (ref "VD30") (pin "2") (pinfunction "C_2") (pintype "passive"))
      (node (ref "VD32") (pin "2") (pinfunction "C_2") (pintype "passive"))
      (node (ref "VD34") (pin "2") (pinfunction "C_2") (pintype "passive"))
      (node (ref "VD36") (pin "2") (pinfunction "C_2") (pintype "passive"))
      (node (ref "VT3") (pin "3") (pinfunction "D_3") (pintype "passive"))
    )
    (net (code "29") (name "Net-(VD21-A)") (class "Default")
      (node (ref "R31") (pin "1") (pinfunction "1_1") (pintype "passive"))
      (node (ref "VD21") (pin "1") (pinfunction "A_1") (pintype "passive"))
    )
    (net (code "30") (name "Net-(VD21-C)") (class "Default")
      (node (ref "VD21") (pin "2") (pinfunction "C_2") (pintype "passive"))
      (node (ref "VD23") (pin "2") (pinfunction "C_2") (pintype "passive"))
      (node (ref "VD25") (pin "2") (pinfunction "C_2") (pintype "passive"))
      (node (ref "VD27") (pin "2") (pinfunction "C_2") (pintype "passive"))
      (node (ref "VD29") (pin "2") (pinfunction "C_2") (pintype "passive"))
      (node (ref "VD31") (pin "2") (pinfunction "C_2") (pintype "passive"))
      (node (ref "VD33") (pin "2") (pinfunction "C_2") (pintype "passive"))
      (node (ref "VD35") (pin "2") (pinfunction "C_2") (pintype "passive"))
      (node (ref "VD37") (pin "2") (pinfunction "C_2") (pintype "passive"))
      (node (ref "VT4") (pin "3") (pinfunction "D_3") (pintype "passive"))
    )
    (net (code "31") (name "Net-(VD22-A)") (class "Default")
      (node (ref "R32") (pin "1") (pinfunction "1_1") (pintype "passive"))
      (node (ref "VD22") (pin "1") (pinfunction "A_1") (pintype "passive"))
    )
    (net (code "32") (name "Net-(VD23-A)") (class "Default")
      (node (ref "R33") (pin "1") (pinfunction "1_1") (pintype "passive"))
      (node (ref "VD23") (pin "1") (pinfunction "A_1") (pintype "passive"))
    )
    (net (code "33") (name "Net-(VD24-A)") (class "Default")
      (node (ref "R34") (pin "1") (pinfunction "1_1") (pintype "passive"))
      (node (ref "VD24") (pin "1") (pinfunction "A_1") (pintype "passive"))
    )
    (net (code "34") (name "Net-(VD25-A)") (class "Default")
      (node (ref "R35") (pin "1") (pinfunction "1_1") (pintype "passive"))
      (node (ref "VD25") (pin "1") (pinfunction "A_1") (pintype "passive"))
    )
    (net (code "35") (name "Net-(VD26-A)") (class "Default")
      (node (ref "R38") (pin "1") (pinfunction "1_1") (pintype "passive"))
      (node (ref "VD26") (pin "1") (pinfunction "A_1") (pintype "passive"))
    )
    (net (code "36") (name "Net-(VD27-A)") (class "Default")
      (node (ref "R39") (pin "1") (pinfunction "1_1") (pintype "passive"))
      (node (ref "VD27") (pin "1") (pinfunction "A_1") (pintype "passive"))
    )
    (net (code "37") (name "Net-(VD28-A)") (class "Default")
      (node (ref "R42") (pin "1") (pinfunction "1_1") (pintype "passive"))
      (node (ref "VD28") (pin "1") (pinfunction "A_1") (pintype "passive"))
    )
    (net (code "38") (name "Net-(VD29-A)") (class "Default")
      (node (ref "R43") (pin "1") (pinfunction "1_1") (pintype "passive"))
      (node (ref "VD29") (pin "1") (pinfunction "A_1") (pintype "passive"))
    )
    (net (code "39") (name "Net-(VD30-A)") (class "Default")
      (node (ref "R44") (pin "1") (pinfunction "1_1") (pintype "passive"))
      (node (ref "VD30") (pin "1") (pinfunction "A_1") (pintype "passive"))
    )
    (net (code "40") (name "Net-(VD31-A)") (class "Default")
      (node (ref "R45") (pin "1") (pinfunction "1_1") (pintype "passive"))
      (node (ref "VD31") (pin "1") (pinfunction "A_1") (pintype "passive"))
    )
    (net (code "41") (name "Net-(VD32-A)") (class "Default")
      (node (ref "R46") (pin "1") (pinfunction "1_1") (pintype "passive"))
      (node (ref "VD32") (pin "1") (pinfunction "A_1") (pintype "passive"))
    )
    (net (code "42") (name "Net-(VD33-A)") (class "Default")
      (node (ref "R47") (pin "1") (pinfunction "1_1") (pintype "passive"))
      (node (ref "VD33") (pin "1") (pinfunction "A_1") (pintype "passive"))
    )
    (net (code "43") (name "Net-(VD34-A)") (class "Default")
      (node (ref "R48") (pin "1") (pinfunction "1_1") (pintype "passive"))
      (node (ref "VD34") (pin "1") (pinfunction "A_1") (pintype "passive"))
    )
    (net (code "44") (name "Net-(VD35-A)") (class "Default")
      (node (ref "R49") (pin "1") (pinfunction "1_1") (pintype "passive"))
      (node (ref "VD35") (pin "1") (pinfunction "A_1") (pintype "passive"))
    )
    (net (code "45") (name "Net-(VD36-A)") (class "Default")
      (node (ref "R50") (pin "1") (pinfunction "1_1") (pintype "passive"))
      (node (ref "VD36") (pin "1") (pinfunction "A_1") (pintype "passive"))
    )
    (net (code "46") (name "Net-(VD37-A)") (class "Default")
      (node (ref "R51") (pin "1") (pinfunction "1_1") (pintype "passive"))
      (node (ref "VD37") (pin "1") (pinfunction "A_1") (pintype "passive"))
    )
    (net (code "47") (name "Net-(VT1-G)") (class "Default")
      (node (ref "R14") (pin "2") (pinfunction "2_2") (pintype "passive"))
      (node (ref "R18") (pin "2") (pinfunction "2_2") (pintype "passive"))
      (node (ref "VT1") (pin "1") (pinfunction "G_1") (pintype "passive"))
    )
    (net (code "48") (name "Net-(VT2-G)") (class "Default")
      (node (ref "R15") (pin "2") (pinfunction "2_2") (pintype "passive"))
      (node (ref "R19") (pin "2") (pinfunction "2_2") (pintype "passive"))
      (node (ref "VT2") (pin "1") (pinfunction "G_1") (pintype "passive"))
    )
    (net (code "49") (name "Net-(VT3-G)") (class "Default")
      (node (ref "R36") (pin "2") (pinfunction "2_2") (pintype "passive"))
      (node (ref "R40") (pin "2") (pinfunction "2_2") (pintype "passive"))
      (node (ref "VT3") (pin "1") (pinfunction "G_1") (pintype "passive"))
    )
    (net (code "50") (name "Net-(VT4-G)") (class "Default")
      (node (ref "R37") (pin "2") (pinfunction "2_2") (pintype "passive"))
      (node (ref "R41") (pin "2") (pinfunction "2_2") (pintype "passive"))
      (node (ref "VT4") (pin "1") (pinfunction "G_1") (pintype "passive"))
    )
  )
)
